# ZB3.net
KiCad netlist of a schematic drawn in Altium Designer
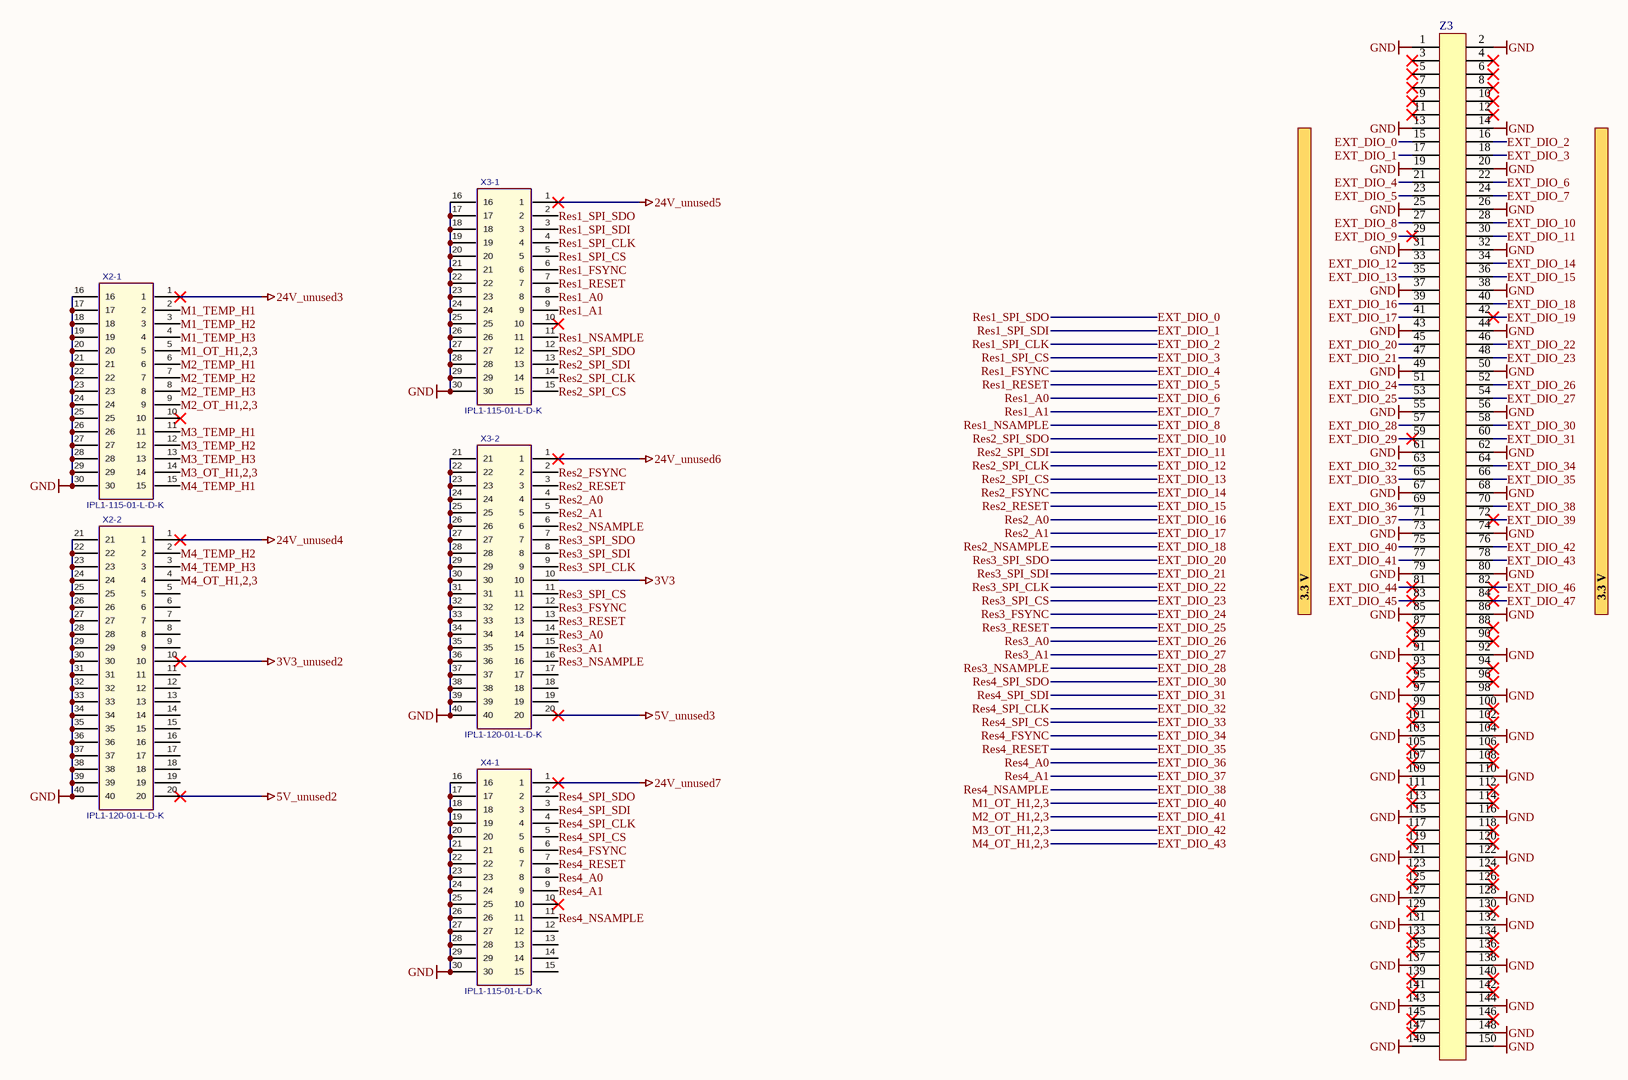
[diagram p0: ZB3.SchDoc]

(export (version "E")
  (design (tool "Eeschema 10.0.6"))
  (components
    (comp (ref "X2-1")
      (value "IPL1-115-01-L-D-K")
      (footprint "IPL1-115-01-YYY-D-K")
      (description "2.54 mm Double Row Terminal Assembly")
      (fields (field (name "MANUFACTURER") "SAMTEC") (field (name "CREATED FROM") "MGremer"))
      (libsource (lib "user") (part "IPL1-115-01-XX-D-XX"))
    )
    (comp (ref "X2-2")
      (value "IPL1-120-01-L-D-K")
      (footprint "SAMTEC_IPL1-120-01-X-D-K")
      (description "Terminal Assembly, Double Row, Thru-Hole, 2.54 mm x 2.54 mm Pitch, 40 Pins")
      (fields (field (name "MANUFACTURER") "SAMTEC") (field (name "CREATED FROM") "PBaumann"))
      (libsource (lib "user") (part "IPL1-120-01-XX-D-XX"))
    )
    (comp (ref "X3-1")
      (value "IPL1-115-01-L-D-K")
      (footprint "IPL1-115-01-YYY-D-K")
      (description "2.54 mm Double Row Terminal Assembly")
      (fields (field (name "MANUFACTURER") "SAMTEC") (field (name "CREATED FROM") "MGremer"))
      (libsource (lib "user") (part "IPL1-115-01-XX-D-XX"))
    )
    (comp (ref "X3-2")
      (value "IPL1-120-01-L-D-K")
      (footprint "SAMTEC_IPL1-120-01-X-D-K")
      (description "Terminal Assembly, Double Row, Thru-Hole, 2.54 mm x 2.54 mm Pitch, 40 Pins")
      (fields (field (name "MANUFACTURER") "SAMTEC") (field (name "CREATED FROM") "PBaumann"))
      (libsource (lib "user") (part "IPL1-120-01-XX-D-XX"))
    )
    (comp (ref "X4-1")
      (value "IPL1-115-01-L-D-K")
      (footprint "IPL1-115-01-YYY-D-K")
      (description "2.54 mm Double Row Terminal Assembly")
      (fields (field (name "MANUFACTURER") "SAMTEC") (field (name "CREATED FROM") "MGremer"))
      (libsource (lib "user") (part "IPL1-115-01-XX-D-XX"))
    )
    (comp (ref "Z3")
      (value "~")
      (footprint "ERM8-075-02.0-L-DV")
      (description "0.80 mm Edge Rate Rugged High Speed")
      (fields
        (field (name "MANUFACTURER PART NUMBER") "ERM8-075-02.0-L-DV-TR")
        (field (name "MANUFACTURER") "SAMTEC")
        (field (name "CREATED FROM") "AGeiger")
      )
      (libsource (lib "user") (part "CON-150"))
    )
  )
  (nets
    (net (code "1") (name "/EXT_DIO_0") (class "Default")
      (node (ref "X3-1") (pin "2") (pinfunction "2_2") (pintype "passive"))
      (node (ref "Z3") (pin "15") (pinfunction "15_15") (pintype "passive"))
    )
    (net (code "2") (name "/EXT_DIO_1") (class "Default")
      (node (ref "X3-1") (pin "3") (pinfunction "3_3") (pintype "passive"))
      (node (ref "Z3") (pin "17") (pinfunction "17_17") (pintype "passive"))
    )
    (net (code "3") (name "/EXT_DIO_2") (class "Default")
      (node (ref "X3-1") (pin "4") (pinfunction "4_4") (pintype "passive"))
      (node (ref "Z3") (pin "16") (pinfunction "16_16") (pintype "passive"))
    )
    (net (code "4") (name "/EXT_DIO_3") (class "Default")
      (node (ref "X3-1") (pin "5") (pinfunction "5_5") (pintype "passive"))
      (node (ref "Z3") (pin "18") (pinfunction "18_18") (pintype "passive"))
    )
    (net (code "5") (name "/EXT_DIO_4") (class "Default")
      (node (ref "X3-1") (pin "6") (pinfunction "6_6") (pintype "passive"))
      (node (ref "Z3") (pin "21") (pinfunction "21_21") (pintype "passive"))
    )
    (net (code "6") (name "/EXT_DIO_5") (class "Default")
      (node (ref "X3-1") (pin "7") (pinfunction "7_7") (pintype "passive"))
      (node (ref "Z3") (pin "23") (pinfunction "23_23") (pintype "passive"))
    )
    (net (code "7") (name "/EXT_DIO_6") (class "Default")
      (node (ref "X3-1") (pin "8") (pinfunction "8_8") (pintype "passive"))
      (node (ref "Z3") (pin "22") (pinfunction "22_22") (pintype "passive"))
    )
    (net (code "8") (name "/EXT_DIO_7") (class "Default")
      (node (ref "X3-1") (pin "9") (pinfunction "9_9") (pintype "passive"))
      (node (ref "Z3") (pin "24") (pinfunction "24_24") (pintype "passive"))
    )
    (net (code "9") (name "/EXT_DIO_8") (class "Default")
      (node (ref "X3-1") (pin "11") (pinfunction "11_11") (pintype "passive"))
      (node (ref "Z3") (pin "27") (pinfunction "27_27") (pintype "passive"))
    )
    (net (code "10") (name "/EXT_DIO_9") (class "Default")
      (node (ref "Z3") (pin "29") (pinfunction "29_29") (pintype "passive+no_connect"))
    )
    (net (code "11") (name "/EXT_DIO_10") (class "Default")
      (node (ref "X3-1") (pin "12") (pinfunction "12_12") (pintype "passive"))
      (node (ref "Z3") (pin "28") (pinfunction "28_28") (pintype "passive"))
    )
    (net (code "12") (name "/EXT_DIO_11") (class "Default")
      (node (ref "X3-1") (pin "13") (pinfunction "13_13") (pintype "passive"))
      (node (ref "Z3") (pin "30") (pinfunction "30_30") (pintype "passive"))
    )
    (net (code "13") (name "/EXT_DIO_12") (class "Default")
      (node (ref "X3-1") (pin "14") (pinfunction "14_14") (pintype "passive"))
      (node (ref "Z3") (pin "33") (pinfunction "33_33") (pintype "passive"))
    )
    (net (code "14") (name "/EXT_DIO_13") (class "Default")
      (node (ref "X3-1") (pin "15") (pinfunction "15_15") (pintype "passive"))
      (node (ref "Z3") (pin "35") (pinfunction "35_35") (pintype "passive"))
    )
    (net (code "15") (name "/EXT_DIO_14") (class "Default")
      (node (ref "X3-2") (pin "2") (pinfunction "2_2") (pintype "passive"))
      (node (ref "Z3") (pin "34") (pinfunction "34_34") (pintype "passive"))
    )
    (net (code "16") (name "/EXT_DIO_15") (class "Default")
      (node (ref "X3-2") (pin "3") (pinfunction "3_3") (pintype "passive"))
      (node (ref "Z3") (pin "36") (pinfunction "36_36") (pintype "passive"))
    )
    (net (code "17") (name "/EXT_DIO_16") (class "Default")
      (node (ref "X3-2") (pin "4") (pinfunction "4_4") (pintype "passive"))
      (node (ref "Z3") (pin "39") (pinfunction "39_39") (pintype "passive"))
    )
    (net (code "18") (name "/EXT_DIO_17") (class "Default")
      (node (ref "X3-2") (pin "5") (pinfunction "5_5") (pintype "passive"))
      (node (ref "Z3") (pin "41") (pinfunction "41_41") (pintype "passive"))
    )
    (net (code "19") (name "/EXT_DIO_18") (class "Default")
      (node (ref "X3-2") (pin "6") (pinfunction "6_6") (pintype "passive"))
      (node (ref "Z3") (pin "40") (pinfunction "40_40") (pintype "passive"))
    )
    (net (code "20") (name "/EXT_DIO_19") (class "Default")
      (node (ref "Z3") (pin "42") (pinfunction "42_42") (pintype "passive+no_connect"))
    )
    (net (code "21") (name "/EXT_DIO_20") (class "Default")
      (node (ref "X3-2") (pin "7") (pinfunction "7_7") (pintype "passive"))
      (node (ref "Z3") (pin "45") (pinfunction "45_45") (pintype "passive"))
    )
    (net (code "22") (name "/EXT_DIO_21") (class "Default")
      (node (ref "X3-2") (pin "8") (pinfunction "8_8") (pintype "passive"))
      (node (ref "Z3") (pin "47") (pinfunction "47_47") (pintype "passive"))
    )
    (net (code "23") (name "/EXT_DIO_22") (class "Default")
      (node (ref "X3-2") (pin "9") (pinfunction "9_9") (pintype "passive"))
      (node (ref "Z3") (pin "46") (pinfunction "46_46") (pintype "passive"))
    )
    (net (code "24") (name "/EXT_DIO_23") (class "Default")
      (node (ref "X3-2") (pin "11") (pinfunction "11_11") (pintype "passive"))
      (node (ref "Z3") (pin "48") (pinfunction "48_48") (pintype "passive"))
    )
    (net (code "25") (name "/EXT_DIO_24") (class "Default")
      (node (ref "X3-2") (pin "12") (pinfunction "12_12") (pintype "passive"))
      (node (ref "Z3") (pin "51") (pinfunction "51_51") (pintype "passive"))
    )
    (net (code "26") (name "/EXT_DIO_25") (class "Default")
      (node (ref "X3-2") (pin "13") (pinfunction "13_13") (pintype "passive"))
      (node (ref "Z3") (pin "53") (pinfunction "53_53") (pintype "passive"))
    )
    (net (code "27") (name "/EXT_DIO_26") (class "Default")
      (node (ref "X3-2") (pin "14") (pinfunction "14_14") (pintype "passive"))
      (node (ref "Z3") (pin "52") (pinfunction "52_52") (pintype "passive"))
    )
    (net (code "28") (name "/EXT_DIO_27") (class "Default")
      (node (ref "X3-2") (pin "15") (pinfunction "15_15") (pintype "passive"))
      (node (ref "Z3") (pin "54") (pinfunction "54_54") (pintype "passive"))
    )
    (net (code "29") (name "/EXT_DIO_28") (class "Default")
      (node (ref "X3-2") (pin "16") (pinfunction "16_16") (pintype "passive"))
      (node (ref "Z3") (pin "57") (pinfunction "57_57") (pintype "passive"))
    )
    (net (code "30") (name "/EXT_DIO_29") (class "Default")
      (node (ref "Z3") (pin "59") (pinfunction "59_59") (pintype "passive+no_connect"))
    )
    (net (code "31") (name "/EXT_DIO_30") (class "Default")
      (node (ref "X4-1") (pin "2") (pinfunction "2_2") (pintype "passive"))
      (node (ref "Z3") (pin "58") (pinfunction "58_58") (pintype "passive"))
    )
    (net (code "32") (name "/EXT_DIO_31") (class "Default")
      (node (ref "X4-1") (pin "3") (pinfunction "3_3") (pintype "passive"))
      (node (ref "Z3") (pin "60") (pinfunction "60_60") (pintype "passive"))
    )
    (net (code "33") (name "/EXT_DIO_32") (class "Default")
      (node (ref "X4-1") (pin "4") (pinfunction "4_4") (pintype "passive"))
      (node (ref "Z3") (pin "63") (pinfunction "63_63") (pintype "passive"))
    )
    (net (code "34") (name "/EXT_DIO_33") (class "Default")
      (node (ref "X4-1") (pin "5") (pinfunction "5_5") (pintype "passive"))
      (node (ref "Z3") (pin "65") (pinfunction "65_65") (pintype "passive"))
    )
    (net (code "35") (name "/EXT_DIO_34") (class "Default")
      (node (ref "X4-1") (pin "6") (pinfunction "6_6") (pintype "passive"))
      (node (ref "Z3") (pin "64") (pinfunction "64_64") (pintype "passive"))
    )
    (net (code "36") (name "/EXT_DIO_35") (class "Default")
      (node (ref "X4-1") (pin "7") (pinfunction "7_7") (pintype "passive"))
      (node (ref "Z3") (pin "66") (pinfunction "66_66") (pintype "passive"))
    )
    (net (code "37") (name "/EXT_DIO_36") (class "Default")
      (node (ref "X4-1") (pin "8") (pinfunction "8_8") (pintype "passive"))
      (node (ref "Z3") (pin "69") (pinfunction "69_69") (pintype "passive"))
    )
    (net (code "38") (name "/EXT_DIO_37") (class "Default")
      (node (ref "X4-1") (pin "9") (pinfunction "9_9") (pintype "passive"))
      (node (ref "Z3") (pin "71") (pinfunction "71_71") (pintype "passive"))
    )
    (net (code "39") (name "/EXT_DIO_38") (class "Default")
      (node (ref "X4-1") (pin "11") (pinfunction "11_11") (pintype "passive"))
      (node (ref "Z3") (pin "70") (pinfunction "70_70") (pintype "passive"))
    )
    (net (code "40") (name "/EXT_DIO_39") (class "Default")
      (node (ref "Z3") (pin "72") (pinfunction "72_72") (pintype "passive+no_connect"))
    )
    (net (code "41") (name "/EXT_DIO_40") (class "Default")
      (node (ref "X2-1") (pin "5") (pinfunction "5_5") (pintype "passive"))
      (node (ref "Z3") (pin "75") (pinfunction "75_75") (pintype "passive"))
    )
    (net (code "42") (name "/EXT_DIO_41") (class "Default")
      (node (ref "X2-1") (pin "9") (pinfunction "9_9") (pintype "passive"))
      (node (ref "Z3") (pin "77") (pinfunction "77_77") (pintype "passive"))
    )
    (net (code "43") (name "/EXT_DIO_42") (class "Default")
      (node (ref "X2-1") (pin "14") (pinfunction "14_14") (pintype "passive"))
      (node (ref "Z3") (pin "76") (pinfunction "76_76") (pintype "passive"))
    )
    (net (code "44") (name "/EXT_DIO_43") (class "Default")
      (node (ref "X2-2") (pin "4") (pinfunction "4_4") (pintype "passive"))
      (node (ref "Z3") (pin "78") (pinfunction "78_78") (pintype "passive"))
    )
    (net (code "45") (name "/EXT_DIO_44") (class "Default")
      (node (ref "Z3") (pin "81") (pinfunction "81_81") (pintype "passive+no_connect"))
    )
    (net (code "46") (name "/EXT_DIO_45") (class "Default")
      (node (ref "Z3") (pin "83") (pinfunction "83_83") (pintype "passive+no_connect"))
    )
    (net (code "47") (name "/EXT_DIO_46") (class "Default")
      (node (ref "Z3") (pin "82") (pinfunction "82_82") (pintype "passive+no_connect"))
    )
    (net (code "48") (name "/EXT_DIO_47") (class "Default")
      (node (ref "Z3") (pin "84") (pinfunction "84_84") (pintype "passive+no_connect"))
    )
    (net (code "49") (name "/M1_TEMP_H1") (class "Default")
      (node (ref "X2-1") (pin "2") (pinfunction "2_2") (pintype "passive"))
    )
    (net (code "50") (name "/M1_TEMP_H2") (class "Default")
      (node (ref "X2-1") (pin "3") (pinfunction "3_3") (pintype "passive"))
    )
    (net (code "51") (name "/M1_TEMP_H3") (class "Default")
      (node (ref "X2-1") (pin "4") (pinfunction "4_4") (pintype "passive"))
    )
    (net (code "52") (name "/M2_TEMP_H1") (class "Default")
      (node (ref "X2-1") (pin "6") (pinfunction "6_6") (pintype "passive"))
    )
    (net (code "53") (name "/M2_TEMP_H2") (class "Default")
      (node (ref "X2-1") (pin "7") (pinfunction "7_7") (pintype "passive"))
    )
    (net (code "54") (name "/M2_TEMP_H3") (class "Default")
      (node (ref "X2-1") (pin "8") (pinfunction "8_8") (pintype "passive"))
    )
    (net (code "55") (name "/M3_TEMP_H1") (class "Default")
      (node (ref "X2-1") (pin "11") (pinfunction "11_11") (pintype "passive"))
    )
    (net (code "56") (name "/M3_TEMP_H2") (class "Default")
      (node (ref "X2-1") (pin "12") (pinfunction "12_12") (pintype "passive"))
    )
    (net (code "57") (name "/M3_TEMP_H3") (class "Default")
      (node (ref "X2-1") (pin "13") (pinfunction "13_13") (pintype "passive"))
    )
    (net (code "58") (name "/M4_TEMP_H1") (class "Default")
      (node (ref "X2-1") (pin "15") (pinfunction "15_15") (pintype "passive"))
    )
    (net (code "59") (name "/M4_TEMP_H2") (class "Default")
      (node (ref "X2-2") (pin "2") (pinfunction "2_2") (pintype "passive"))
    )
    (net (code "60") (name "/M4_TEMP_H3") (class "Default")
      (node (ref "X2-2") (pin "3") (pinfunction "3_3") (pintype "passive"))
    )
    (net (code "61") (name "3V3") (class "Default")
      (node (ref "X3-2") (pin "10") (pinfunction "10_10") (pintype "passive"))
    )
    (net (code "62") (name "3V3_unused2") (class "Default")
      (node (ref "X2-2") (pin "10") (pinfunction "10_10") (pintype "passive"))
    )
    (net (code "63") (name "5V_unused2") (class "Default")
      (node (ref "X2-2") (pin "20") (pinfunction "20_20") (pintype "passive"))
    )
    (net (code "64") (name "5V_unused3") (class "Default")
      (node (ref "X3-2") (pin "20") (pinfunction "20_20") (pintype "passive"))
    )
    (net (code "65") (name "24V_unused3") (class "Default")
      (node (ref "X2-1") (pin "1") (pinfunction "1_1") (pintype "passive"))
    )
    (net (code "66") (name "24V_unused4") (class "Default")
      (node (ref "X2-2") (pin "1") (pinfunction "1_1") (pintype "passive"))
    )
    (net (code "67") (name "24V_unused5") (class "Default")
      (node (ref "X3-1") (pin "1") (pinfunction "1_1") (pintype "passive"))
    )
    (net (code "68") (name "24V_unused6") (class "Default")
      (node (ref "X3-2") (pin "1") (pinfunction "1_1") (pintype "passive"))
    )
    (net (code "69") (name "24V_unused7") (class "Default")
      (node (ref "X4-1") (pin "1") (pinfunction "1_1") (pintype "passive"))
    )
    (net (code "70") (name "GND") (class "Default")
      (node (ref "X2-1") (pin "16") (pinfunction "16_16") (pintype "passive"))
      (node (ref "X2-1") (pin "17") (pinfunction "17_17") (pintype "passive"))
      (node (ref "X2-1") (pin "18") (pinfunction "18_18") (pintype "passive"))
      (node (ref "X2-1") (pin "19") (pinfunction "19_19") (pintype "passive"))
      (node (ref "X2-1") (pin "20") (pinfunction "20_20") (pintype "passive"))
      (node (ref "X2-1") (pin "21") (pinfunction "21_21") (pintype "passive"))
      (node (ref "X2-1") (pin "22") (pinfunction "22_22") (pintype "passive"))
      (node (ref "X2-1") (pin "23") (pinfunction "23_23") (pintype "passive"))
      (node (ref "X2-1") (pin "24") (pinfunction "24_24") (pintype "passive"))
      (node (ref "X2-1") (pin "25") (pinfunction "25_25") (pintype "passive"))
      (node (ref "X2-1") (pin "26") (pinfunction "26_26") (pintype "passive"))
      (node (ref "X2-1") (pin "27") (pinfunction "27_27") (pintype "passive"))
      (node (ref "X2-1") (pin "28") (pinfunction "28_28") (pintype "passive"))
      (node (ref "X2-1") (pin "29") (pinfunction "29_29") (pintype "passive"))
      (node (ref "X2-1") (pin "30") (pinfunction "30_30") (pintype "passive"))
      (node (ref "X2-2") (pin "21") (pinfunction "21_21") (pintype "passive"))
      (node (ref "X2-2") (pin "22") (pinfunction "22_22") (pintype "passive"))
      (node (ref "X2-2") (pin "23") (pinfunction "23_23") (pintype "passive"))
      (node (ref "X2-2") (pin "24") (pinfunction "24_24") (pintype "passive"))
      (node (ref "X2-2") (pin "25") (pinfunction "25_25") (pintype "passive"))
      (node (ref "X2-2") (pin "26") (pinfunction "26_26") (pintype "passive"))
      (node (ref "X2-2") (pin "27") (pinfunction "27_27") (pintype "passive"))
      (node (ref "X2-2") (pin "28") (pinfunction "28_28") (pintype "passive"))
      (node (ref "X2-2") (pin "29") (pinfunction "29_29") (pintype "passive"))
      (node (ref "X2-2") (pin "30") (pinfunction "30_30") (pintype "passive"))
      (node (ref "X2-2") (pin "31") (pinfunction "31_31") (pintype "passive"))
      (node (ref "X2-2") (pin "32") (pinfunction "32_32") (pintype "passive"))
      (node (ref "X2-2") (pin "33") (pinfunction "33_33") (pintype "passive"))
      (node (ref "X2-2") (pin "34") (pinfunction "34_34") (pintype "passive"))
      (node (ref "X2-2") (pin "35") (pinfunction "35_35") (pintype "passive"))
      (node (ref "X2-2") (pin "36") (pinfunction "36_36") (pintype "passive"))
      (node (ref "X2-2") (pin "37") (pinfunction "37_37") (pintype "passive"))
      (node (ref "X2-2") (pin "38") (pinfunction "38_38") (pintype "passive"))
      (node (ref "X2-2") (pin "39") (pinfunction "39_39") (pintype "passive"))
      (node (ref "X2-2") (pin "40") (pinfunction "40_40") (pintype "passive"))
      (node (ref "X3-1") (pin "16") (pinfunction "16_16") (pintype "passive"))
      (node (ref "X3-1") (pin "17") (pinfunction "17_17") (pintype "passive"))
      (node (ref "X3-1") (pin "18") (pinfunction "18_18") (pintype "passive"))
      (node (ref "X3-1") (pin "19") (pinfunction "19_19") (pintype "passive"))
      (node (ref "X3-1") (pin "20") (pinfunction "20_20") (pintype "passive"))
      (node (ref "X3-1") (pin "21") (pinfunction "21_21") (pintype "passive"))
      (node (ref "X3-1") (pin "22") (pinfunction "22_22") (pintype "passive"))
      (node (ref "X3-1") (pin "23") (pinfunction "23_23") (pintype "passive"))
      (node (ref "X3-1") (pin "24") (pinfunction "24_24") (pintype "passive"))
      (node (ref "X3-1") (pin "25") (pinfunction "25_25") (pintype "passive"))
      (node (ref "X3-1") (pin "26") (pinfunction "26_26") (pintype "passive"))
      (node (ref "X3-1") (pin "27") (pinfunction "27_27") (pintype "passive"))
      (node (ref "X3-1") (pin "28") (pinfunction "28_28") (pintype "passive"))
      (node (ref "X3-1") (pin "29") (pinfunction "29_29") (pintype "passive"))
      (node (ref "X3-1") (pin "30") (pinfunction "30_30") (pintype "passive"))
      (node (ref "X3-2") (pin "21") (pinfunction "21_21") (pintype "passive"))
      (node (ref "X3-2") (pin "22") (pinfunction "22_22") (pintype "passive"))
      (node (ref "X3-2") (pin "23") (pinfunction "23_23") (pintype "passive"))
      (node (ref "X3-2") (pin "24") (pinfunction "24_24") (pintype "passive"))
      (node (ref "X3-2") (pin "25") (pinfunction "25_25") (pintype "passive"))
      (node (ref "X3-2") (pin "26") (pinfunction "26_26") (pintype "passive"))
      (node (ref "X3-2") (pin "27") (pinfunction "27_27") (pintype "passive"))
      (node (ref "X3-2") (pin "28") (pinfunction "28_28") (pintype "passive"))
      (node (ref "X3-2") (pin "29") (pinfunction "29_29") (pintype "passive"))
      (node (ref "X3-2") (pin "30") (pinfunction "30_30") (pintype "passive"))
      (node (ref "X3-2") (pin "31") (pinfunction "31_31") (pintype "passive"))
      (node (ref "X3-2") (pin "32") (pinfunction "32_32") (pintype "passive"))
      (node (ref "X3-2") (pin "33") (pinfunction "33_33") (pintype "passive"))
      (node (ref "X3-2") (pin "34") (pinfunction "34_34") (pintype "passive"))
      (node (ref "X3-2") (pin "35") (pinfunction "35_35") (pintype "passive"))
      (node (ref "X3-2") (pin "36") (pinfunction "36_36") (pintype "passive"))
      (node (ref "X3-2") (pin "37") (pinfunction "37_37") (pintype "passive"))
      (node (ref "X3-2") (pin "38") (pinfunction "38_38") (pintype "passive"))
      (node (ref "X3-2") (pin "39") (pinfunction "39_39") (pintype "passive"))
      (node (ref "X3-2") (pin "40") (pinfunction "40_40") (pintype "passive"))
      (node (ref "X4-1") (pin "16") (pinfunction "16_16") (pintype "passive"))
      (node (ref "X4-1") (pin "17") (pinfunction "17_17") (pintype "passive"))
      (node (ref "X4-1") (pin "18") (pinfunction "18_18") (pintype "passive"))
      (node (ref "X4-1") (pin "19") (pinfunction "19_19") (pintype "passive"))
      (node (ref "X4-1") (pin "20") (pinfunction "20_20") (pintype "passive"))
      (node (ref "X4-1") (pin "21") (pinfunction "21_21") (pintype "passive"))
      (node (ref "X4-1") (pin "22") (pinfunction "22_22") (pintype "passive"))
      (node (ref "X4-1") (pin "23") (pinfunction "23_23") (pintype "passive"))
      (node (ref "X4-1") (pin "24") (pinfunction "24_24") (pintype "passive"))
      (node (ref "X4-1") (pin "25") (pinfunction "25_25") (pintype "passive"))
      (node (ref "X4-1") (pin "26") (pinfunction "26_26") (pintype "passive"))
      (node (ref "X4-1") (pin "27") (pinfunction "27_27") (pintype "passive"))
      (node (ref "X4-1") (pin "28") (pinfunction "28_28") (pintype "passive"))
      (node (ref "X4-1") (pin "29") (pinfunction "29_29") (pintype "passive"))
      (node (ref "X4-1") (pin "30") (pinfunction "30_30") (pintype "passive"))
      (node (ref "Z3") (pin "1") (pinfunction "1_1") (pintype "passive"))
      (node (ref "Z3") (pin "103") (pinfunction "103_103") (pintype "passive"))
      (node (ref "Z3") (pin "104") (pinfunction "104_104") (pintype "passive"))
      (node (ref "Z3") (pin "109") (pinfunction "109_109") (pintype "passive"))
      (node (ref "Z3") (pin "110") (pinfunction "110_110") (pintype "passive"))
      (node (ref "Z3") (pin "115") (pinfunction "115_115") (pintype "passive"))
      (node (ref "Z3") (pin "116") (pinfunction "116_116") (pintype "passive"))
      (node (ref "Z3") (pin "121") (pinfunction "121_121") (pintype "passive"))
      (node (ref "Z3") (pin "122") (pinfunction "122_122") (pintype "passive"))
      (node (ref "Z3") (pin "127") (pinfunction "127_127") (pintype "passive"))
      (node (ref "Z3") (pin "128") (pinfunction "128_128") (pintype "passive"))
      (node (ref "Z3") (pin "13") (pinfunction "13_13") (pintype "passive"))
      (node (ref "Z3") (pin "131") (pinfunction "131_131") (pintype "passive"))
      (node (ref "Z3") (pin "132") (pinfunction "132_132") (pintype "passive"))
      (node (ref "Z3") (pin "137") (pinfunction "137_137") (pintype "passive"))
      (node (ref "Z3") (pin "138") (pinfunction "138_138") (pintype "passive"))
      (node (ref "Z3") (pin "14") (pinfunction "14_14") (pintype "passive"))
      (node (ref "Z3") (pin "143") (pinfunction "143_143") (pintype "passive"))
      (node (ref "Z3") (pin "144") (pinfunction "144_144") (pintype "passive"))
      (node (ref "Z3") (pin "148") (pinfunction "148_148") (pintype "passive"))
      (node (ref "Z3") (pin "149") (pinfunction "149_149") (pintype "passive"))
      (node (ref "Z3") (pin "150") (pinfunction "150_150") (pintype "passive"))
      (node (ref "Z3") (pin "19") (pinfunction "19_19") (pintype "passive"))
      (node (ref "Z3") (pin "2") (pinfunction "2_2") (pintype "passive"))
      (node (ref "Z3") (pin "20") (pinfunction "20_20") (pintype "passive"))
      (node (ref "Z3") (pin "25") (pinfunction "25_25") (pintype "passive"))
      (node (ref "Z3") (pin "26") (pinfunction "26_26") (pintype "passive"))
      (node (ref "Z3") (pin "31") (pinfunction "31_31") (pintype "passive"))
      (node (ref "Z3") (pin "32") (pinfunction "32_32") (pintype "passive"))
      (node (ref "Z3") (pin "37") (pinfunction "37_37") (pintype "passive"))
      (node (ref "Z3") (pin "38") (pinfunction "38_38") (pintype "passive"))
      (node (ref "Z3") (pin "43") (pinfunction "43_43") (pintype "passive"))
      (node (ref "Z3") (pin "44") (pinfunction "44_44") (pintype "passive"))
      (node (ref "Z3") (pin "49") (pinfunction "49_49") (pintype "passive"))
      (node (ref "Z3") (pin "50") (pinfunction "50_50") (pintype "passive"))
      (node (ref "Z3") (pin "55") (pinfunction "55_55") (pintype "passive"))
      (node (ref "Z3") (pin "56") (pinfunction "56_56") (pintype "passive"))
      (node (ref "Z3") (pin "61") (pinfunction "61_61") (pintype "passive"))
      (node (ref "Z3") (pin "62") (pinfunction "62_62") (pintype "passive"))
      (node (ref "Z3") (pin "67") (pinfunction "67_67") (pintype "passive"))
      (node (ref "Z3") (pin "68") (pinfunction "68_68") (pintype "passive"))
      (node (ref "Z3") (pin "73") (pinfunction "73_73") (pintype "passive"))
      (node (ref "Z3") (pin "74") (pinfunction "74_74") (pintype "passive"))
      (node (ref "Z3") (pin "79") (pinfunction "79_79") (pintype "passive"))
      (node (ref "Z3") (pin "80") (pinfunction "80_80") (pintype "passive"))
      (node (ref "Z3") (pin "85") (pinfunction "85_85") (pintype "passive"))
      (node (ref "Z3") (pin "86") (pinfunction "86_86") (pintype "passive"))
      (node (ref "Z3") (pin "91") (pinfunction "91_91") (pintype "passive"))
      (node (ref "Z3") (pin "92") (pinfunction "92_92") (pintype "passive"))
      (node (ref "Z3") (pin "97") (pinfunction "97_97") (pintype "passive"))
      (node (ref "Z3") (pin "98") (pinfunction "98_98") (pintype "passive"))
    )
    (net (code "71") (name "unconnected-(X2-1-Pad10)") (class "Default")
      (node (ref "X2-1") (pin "10") (pinfunction "10_10") (pintype "passive+no_connect"))
    )
    (net (code "72") (name "unconnected-(X2-2-Pad5)") (class "Default")
      (node (ref "X2-2") (pin "5") (pinfunction "5_5") (pintype "passive"))
    )
    (net (code "73") (name "unconnected-(X2-2-Pad6)") (class "Default")
      (node (ref "X2-2") (pin "6") (pinfunction "6_6") (pintype "passive"))
    )
    (net (code "74") (name "unconnected-(X2-2-Pad7)") (class "Default")
      (node (ref "X2-2") (pin "7") (pinfunction "7_7") (pintype "passive"))
    )
    (net (code "75") (name "unconnected-(X2-2-Pad8)") (class "Default")
      (node (ref "X2-2") (pin "8") (pinfunction "8_8") (pintype "passive"))
    )
    (net (code "76") (name "unconnected-(X2-2-Pad9)") (class "Default")
      (node (ref "X2-2") (pin "9") (pinfunction "9_9") (pintype "passive"))
    )
    (net (code "77") (name "unconnected-(X2-2-Pad11)") (class "Default")
      (node (ref "X2-2") (pin "11") (pinfunction "11_11") (pintype "passive"))
    )
    (net (code "78") (name "unconnected-(X2-2-Pad12)") (class "Default")
      (node (ref "X2-2") (pin "12") (pinfunction "12_12") (pintype "passive"))
    )
    (net (code "79") (name "unconnected-(X2-2-Pad13)") (class "Default")
      (node (ref "X2-2") (pin "13") (pinfunction "13_13") (pintype "passive"))
    )
    (net (code "80") (name "unconnected-(X2-2-Pad14)") (class "Default")
      (node (ref "X2-2") (pin "14") (pinfunction "14_14") (pintype "passive"))
    )
    (net (code "81") (name "unconnected-(X2-2-Pad15)") (class "Default")
      (node (ref "X2-2") (pin "15") (pinfunction "15_15") (pintype "passive"))
    )
    (net (code "82") (name "unconnected-(X2-2-Pad16)") (class "Default")
      (node (ref "X2-2") (pin "16") (pinfunction "16_16") (pintype "passive"))
    )
    (net (code "83") (name "unconnected-(X2-2-Pad17)") (class "Default")
      (node (ref "X2-2") (pin "17") (pinfunction "17_17") (pintype "passive"))
    )
    (net (code "84") (name "unconnected-(X2-2-Pad18)") (class "Default")
      (node (ref "X2-2") (pin "18") (pinfunction "18_18") (pintype "passive"))
    )
    (net (code "85") (name "unconnected-(X2-2-Pad19)") (class "Default")
      (node (ref "X2-2") (pin "19") (pinfunction "19_19") (pintype "passive"))
    )
    (net (code "86") (name "unconnected-(X3-1-Pad10)") (class "Default")
      (node (ref "X3-1") (pin "10") (pinfunction "10_10") (pintype "passive+no_connect"))
    )
    (net (code "87") (name "unconnected-(X3-2-Pad17)") (class "Default")
      (node (ref "X3-2") (pin "17") (pinfunction "17_17") (pintype "passive"))
    )
    (net (code "88") (name "unconnected-(X3-2-Pad18)") (class "Default")
      (node (ref "X3-2") (pin "18") (pinfunction "18_18") (pintype "passive"))
    )
    (net (code "89") (name "unconnected-(X3-2-Pad19)") (class "Default")
      (node (ref "X3-2") (pin "19") (pinfunction "19_19") (pintype "passive"))
    )
    (net (code "90") (name "unconnected-(X4-1-Pad10)") (class "Default")
      (node (ref "X4-1") (pin "10") (pinfunction "10_10") (pintype "passive+no_connect"))
    )
    (net (code "91") (name "unconnected-(X4-1-Pad12)") (class "Default")
      (node (ref "X4-1") (pin "12") (pinfunction "12_12") (pintype "passive"))
    )
    (net (code "92") (name "unconnected-(X4-1-Pad13)") (class "Default")
      (node (ref "X4-1") (pin "13") (pinfunction "13_13") (pintype "passive"))
    )
    (net (code "93") (name "unconnected-(X4-1-Pad14)") (class "Default")
      (node (ref "X4-1") (pin "14") (pinfunction "14_14") (pintype "passive"))
    )
    (net (code "94") (name "unconnected-(X4-1-Pad15)") (class "Default")
      (node (ref "X4-1") (pin "15") (pinfunction "15_15") (pintype "passive"))
    )
    (net (code "95") (name "unconnected-(Z3-Pad3)") (class "Default")
      (node (ref "Z3") (pin "3") (pinfunction "3_3") (pintype "passive+no_connect"))
    )
    (net (code "96") (name "unconnected-(Z3-Pad4)") (class "Default")
      (node (ref "Z3") (pin "4") (pinfunction "4_4") (pintype "passive+no_connect"))
    )
    (net (code "97") (name "unconnected-(Z3-Pad5)") (class "Default")
      (node (ref "Z3") (pin "5") (pinfunction "5_5") (pintype "passive+no_connect"))
    )
    (net (code "98") (name "unconnected-(Z3-Pad6)") (class "Default")
      (node (ref "Z3") (pin "6") (pinfunction "6_6") (pintype "passive+no_connect"))
    )
    (net (code "99") (name "unconnected-(Z3-Pad7)") (class "Default")
      (node (ref "Z3") (pin "7") (pinfunction "7_7") (pintype "passive+no_connect"))
    )
    (net (code "100") (name "unconnected-(Z3-Pad8)") (class "Default")
      (node (ref "Z3") (pin "8") (pinfunction "8_8") (pintype "passive+no_connect"))
    )
    (net (code "101") (name "unconnected-(Z3-Pad9)") (class "Default")
      (node (ref "Z3") (pin "9") (pinfunction "9_9") (pintype "passive+no_connect"))
    )
    (net (code "102") (name "unconnected-(Z3-Pad10)") (class "Default")
      (node (ref "Z3") (pin "10") (pinfunction "10_10") (pintype "passive+no_connect"))
    )
    (net (code "103") (name "unconnected-(Z3-Pad11)") (class "Default")
      (node (ref "Z3") (pin "11") (pinfunction "11_11") (pintype "passive+no_connect"))
    )
    (net (code "104") (name "unconnected-(Z3-Pad12)") (class "Default")
      (node (ref "Z3") (pin "12") (pinfunction "12_12") (pintype "passive+no_connect"))
    )
    (net (code "105") (name "unconnected-(Z3-Pad87)") (class "Default")
      (node (ref "Z3") (pin "87") (pinfunction "87_87") (pintype "passive+no_connect"))
    )
    (net (code "106") (name "unconnected-(Z3-Pad88)") (class "Default")
      (node (ref "Z3") (pin "88") (pinfunction "88_88") (pintype "passive+no_connect"))
    )
    (net (code "107") (name "unconnected-(Z3-Pad89)") (class "Default")
      (node (ref "Z3") (pin "89") (pinfunction "89_89") (pintype "passive+no_connect"))
    )
    (net (code "108") (name "unconnected-(Z3-Pad90)") (class "Default")
      (node (ref "Z3") (pin "90") (pinfunction "90_90") (pintype "passive+no_connect"))
    )
    (net (code "109") (name "unconnected-(Z3-Pad93)") (class "Default")
      (node (ref "Z3") (pin "93") (pinfunction "93_93") (pintype "passive+no_connect"))
    )
    (net (code "110") (name "unconnected-(Z3-Pad94)") (class "Default")
      (node (ref "Z3") (pin "94") (pinfunction "94_94") (pintype "passive+no_connect"))
    )
    (net (code "111") (name "unconnected-(Z3-Pad95)") (class "Default")
      (node (ref "Z3") (pin "95") (pinfunction "95_95") (pintype "passive+no_connect"))
    )
    (net (code "112") (name "unconnected-(Z3-Pad96)") (class "Default")
      (node (ref "Z3") (pin "96") (pinfunction "96_96") (pintype "passive+no_connect"))
    )
    (net (code "113") (name "unconnected-(Z3-Pad99)") (class "Default")
      (node (ref "Z3") (pin "99") (pinfunction "99_99") (pintype "passive+no_connect"))
    )
    (net (code "114") (name "unconnected-(Z3-Pad100)") (class "Default")
      (node (ref "Z3") (pin "100") (pinfunction "100_100") (pintype "passive+no_connect"))
    )
    (net (code "115") (name "unconnected-(Z3-Pad101)") (class "Default")
      (node (ref "Z3") (pin "101") (pinfunction "101_101") (pintype "passive+no_connect"))
    )
    (net (code "116") (name "unconnected-(Z3-Pad102)") (class "Default")
      (node (ref "Z3") (pin "102") (pinfunction "102_102") (pintype "passive+no_connect"))
    )
    (net (code "117") (name "unconnected-(Z3-Pad105)") (class "Default")
      (node (ref "Z3") (pin "105") (pinfunction "105_105") (pintype "passive+no_connect"))
    )
    (net (code "118") (name "unconnected-(Z3-Pad106)") (class "Default")
      (node (ref "Z3") (pin "106") (pinfunction "106_106") (pintype "passive+no_connect"))
    )
    (net (code "119") (name "unconnected-(Z3-Pad107)") (class "Default")
      (node (ref "Z3") (pin "107") (pinfunction "107_107") (pintype "passive+no_connect"))
    )
    (net (code "120") (name "unconnected-(Z3-Pad108)") (class "Default")
      (node (ref "Z3") (pin "108") (pinfunction "108_108") (pintype "passive+no_connect"))
    )
    (net (code "121") (name "unconnected-(Z3-Pad111)") (class "Default")
      (node (ref "Z3") (pin "111") (pinfunction "111_111") (pintype "passive+no_connect"))
    )
    (net (code "122") (name "unconnected-(Z3-Pad112)") (class "Default")
      (node (ref "Z3") (pin "112") (pinfunction "112_112") (pintype "passive+no_connect"))
    )
    (net (code "123") (name "unconnected-(Z3-Pad113)") (class "Default")
      (node (ref "Z3") (pin "113") (pinfunction "113_113") (pintype "passive+no_connect"))
    )
    (net (code "124") (name "unconnected-(Z3-Pad114)") (class "Default")
      (node (ref "Z3") (pin "114") (pinfunction "114_114") (pintype "passive+no_connect"))
    )
    (net (code "125") (name "unconnected-(Z3-Pad117)") (class "Default")
      (node (ref "Z3") (pin "117") (pinfunction "117_117") (pintype "passive+no_connect"))
    )
    (net (code "126") (name "unconnected-(Z3-Pad118)") (class "Default")
      (node (ref "Z3") (pin "118") (pinfunction "118_118") (pintype "passive+no_connect"))
    )
    (net (code "127") (name "unconnected-(Z3-Pad119)") (class "Default")
      (node (ref "Z3") (pin "119") (pinfunction "119_119") (pintype "passive+no_connect"))
    )
    (net (code "128") (name "unconnected-(Z3-Pad120)") (class "Default")
      (node (ref "Z3") (pin "120") (pinfunction "120_120") (pintype "passive+no_connect"))
    )
    (net (code "129") (name "unconnected-(Z3-Pad123)") (class "Default")
      (node (ref "Z3") (pin "123") (pinfunction "123_123") (pintype "passive+no_connect"))
    )
    (net (code "130") (name "unconnected-(Z3-Pad124)") (class "Default")
      (node (ref "Z3") (pin "124") (pinfunction "124_124") (pintype "passive+no_connect"))
    )
    (net (code "131") (name "unconnected-(Z3-Pad125)") (class "Default")
      (node (ref "Z3") (pin "125") (pinfunction "125_125") (pintype "passive+no_connect"))
    )
    (net (code "132") (name "unconnected-(Z3-Pad126)") (class "Default")
      (node (ref "Z3") (pin "126") (pinfunction "126_126") (pintype "passive+no_connect"))
    )
    (net (code "133") (name "unconnected-(Z3-Pad129)") (class "Default")
      (node (ref "Z3") (pin "129") (pinfunction "129_129") (pintype "passive+no_connect"))
    )
    (net (code "134") (name "unconnected-(Z3-Pad130)") (class "Default")
      (node (ref "Z3") (pin "130") (pinfunction "130_130") (pintype "passive+no_connect"))
    )
    (net (code "135") (name "unconnected-(Z3-Pad133)") (class "Default")
      (node (ref "Z3") (pin "133") (pinfunction "133_133") (pintype "passive+no_connect"))
    )
    (net (code "136") (name "unconnected-(Z3-Pad134)") (class "Default")
      (node (ref "Z3") (pin "134") (pinfunction "134_134") (pintype "passive+no_connect"))
    )
    (net (code "137") (name "unconnected-(Z3-Pad135)") (class "Default")
      (node (ref "Z3") (pin "135") (pinfunction "135_135") (pintype "passive+no_connect"))
    )
    (net (code "138") (name "unconnected-(Z3-Pad136)") (class "Default")
      (node (ref "Z3") (pin "136") (pinfunction "136_136") (pintype "passive+no_connect"))
    )
    (net (code "139") (name "unconnected-(Z3-Pad139)") (class "Default")
      (node (ref "Z3") (pin "139") (pinfunction "139_139") (pintype "passive+no_connect"))
    )
    (net (code "140") (name "unconnected-(Z3-Pad140)") (class "Default")
      (node (ref "Z3") (pin "140") (pinfunction "140_140") (pintype "passive+no_connect"))
    )
    (net (code "141") (name "unconnected-(Z3-Pad141)") (class "Default")
      (node (ref "Z3") (pin "141") (pinfunction "141_141") (pintype "passive+no_connect"))
    )
    (net (code "142") (name "unconnected-(Z3-Pad142)") (class "Default")
      (node (ref "Z3") (pin "142") (pinfunction "142_142") (pintype "passive+no_connect"))
    )
    (net (code "143") (name "unconnected-(Z3-Pad145)") (class "Default")
      (node (ref "Z3") (pin "145") (pinfunction "145_145") (pintype "passive+no_connect"))
    )
    (net (code "144") (name "unconnected-(Z3-Pad146)") (class "Default")
      (node (ref "Z3") (pin "146") (pinfunction "146_146") (pintype "passive+no_connect"))
    )
    (net (code "145") (name "unconnected-(Z3-Pad147)") (class "Default")
      (node (ref "Z3") (pin "147") (pinfunction "147_147") (pintype "passive+no_connect"))
    )
  )
)
